# Snippet_FT232RL.net
KiCad netlist of a schematic drawn in Altium Designer
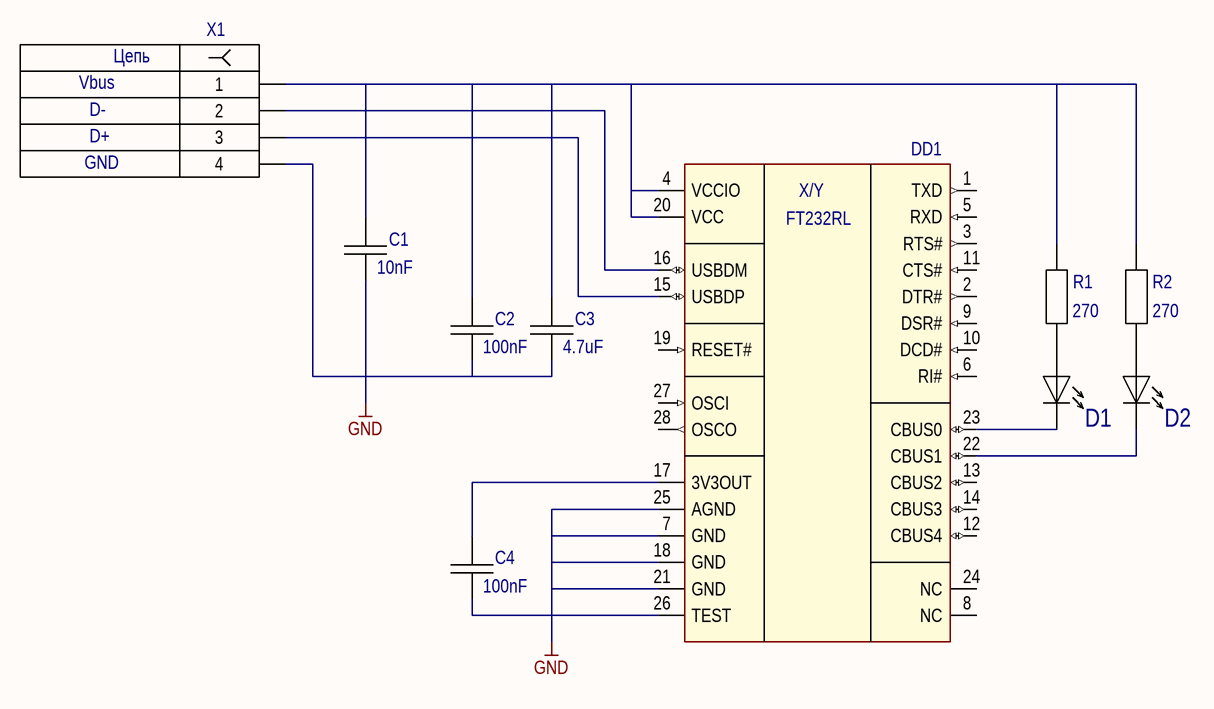
[diagram p0: Snippet_FT232RL.SchDoc]

(export (version "E")
  (design (tool "Eeschema 10.0.6"))
  (components
    (comp (ref "C1")
      (value "10nF")
      (footprint "Capacitor_0805")
      (libsource (lib "Библиотека элементов") (part "Capacitor"))
    )
    (comp (ref "C2")
      (value "100nF")
      (footprint "Capacitor_0805")
      (libsource (lib "Библиотека элементов") (part "Capacitor"))
    )
    (comp (ref "C3")
      (value "4.7uF")
      (footprint "Capacitor_0805")
      (libsource (lib "Библиотека элементов") (part "Capacitor"))
    )
    (comp (ref "C4")
      (value "100nF")
      (footprint "Capacitor_0805")
      (libsource (lib "Библиотека элементов") (part "Capacitor"))
    )
    (comp (ref "D1")
      (value "LED_2.54mm_R")
      (footprint "LED_2.54mm_R")
      (libsource (lib "Библиотека элементов") (part "LED_2.54mm_R"))
    )
    (comp (ref "D2")
      (value "LED_2.54mm_G")
      (footprint "LED_2.54mm_G")
      (libsource (lib "Библиотека элементов") (part "LED_2.54mm_G"))
    )
    (comp (ref "DD1")
      (value "FT232RL")
      (footprint "FT232RL")
      (libsource (lib "Библиотека элементов") (part "FT232RL"))
    )
    (comp (ref "R1")
      (value "270")
      (footprint "RESISTOR_SMD0805")
      (libsource (lib "Библиотека элементов") (part "Resistor_0805"))
    )
    (comp (ref "R2")
      (value "270")
      (footprint "RESISTOR_SMD0805")
      (libsource (lib "Библиотека элементов") (part "Resistor_0805"))
    )
    (comp (ref "X1")
      (value "Connector_USB_typeB")
      (footprint "Connector_USB_B")
      (libsource (lib "Библиотека элементов") (part "Connector_USB_typeB"))
    )
  )
  (nets
    (net (code "1") (name "GND") (class "Default")
      (node (ref "C1") (pin "2") (pinfunction "2_2") (pintype "passive"))
      (node (ref "C2") (pin "2") (pinfunction "2_2") (pintype "passive"))
      (node (ref "C3") (pin "2") (pinfunction "2_2") (pintype "passive"))
      (node (ref "C4") (pin "2") (pinfunction "2_2") (pintype "passive"))
      (node (ref "DD1") (pin "18") (pinfunction "GND_18") (pintype "power_in"))
      (node (ref "DD1") (pin "21") (pinfunction "GND_21") (pintype "power_in"))
      (node (ref "DD1") (pin "25") (pinfunction "AGND_25") (pintype "power_in"))
      (node (ref "DD1") (pin "26") (pinfunction "TEST_26") (pintype "power_in"))
      (node (ref "DD1") (pin "7") (pinfunction "GND_7") (pintype "power_in"))
      (node (ref "X1") (pin "4") (pinfunction "4_4") (pintype "passive"))
    )
    (net (code "2") (name "Net-(D1-Pad2)") (class "Default")
      (node (ref "D1") (pin "2") (pinfunction "2_2") (pintype "passive"))
      (node (ref "R1") (pin "1") (pinfunction "1_1") (pintype "passive"))
    )
    (net (code "3") (name "Net-(D2-Pad2)") (class "Default")
      (node (ref "D2") (pin "2") (pinfunction "2_2") (pintype "passive"))
      (node (ref "R2") (pin "1") (pinfunction "1_1") (pintype "passive"))
    )
    (net (code "4") (name "Net-(DD1-3V3OUT)") (class "Default")
      (node (ref "C4") (pin "1") (pinfunction "1_1") (pintype "passive"))
      (node (ref "DD1") (pin "17") (pinfunction "3V3OUT_17") (pintype "power_in"))
    )
    (net (code "5") (name "Net-(DD1-CBUS0)") (class "Default")
      (node (ref "D1") (pin "1") (pinfunction "1_1") (pintype "passive"))
      (node (ref "DD1") (pin "23") (pinfunction "CBUS0_23") (pintype "bidirectional"))
    )
    (net (code "6") (name "Net-(DD1-CBUS1)") (class "Default")
      (node (ref "D2") (pin "1") (pinfunction "1_1") (pintype "passive"))
      (node (ref "DD1") (pin "22") (pinfunction "CBUS1_22") (pintype "bidirectional"))
    )
    (net (code "7") (name "Net-(DD1-USBDM)") (class "Default")
      (node (ref "DD1") (pin "16") (pinfunction "USBDM_16") (pintype "bidirectional"))
      (node (ref "X1") (pin "2") (pinfunction "2_2") (pintype "passive"))
    )
    (net (code "8") (name "Net-(DD1-USBDP)") (class "Default")
      (node (ref "DD1") (pin "15") (pinfunction "USBDP_15") (pintype "bidirectional"))
      (node (ref "X1") (pin "3") (pinfunction "3_3") (pintype "passive"))
    )
    (net (code "9") (name "Net-(DD1-VCC)") (class "Default")
      (node (ref "C1") (pin "1") (pinfunction "1_1") (pintype "passive"))
      (node (ref "C2") (pin "1") (pinfunction "1_1") (pintype "passive"))
      (node (ref "C3") (pin "1") (pinfunction "1_1") (pintype "passive"))
      (node (ref "DD1") (pin "20") (pinfunction "VCC_20") (pintype "power_in"))
      (node (ref "DD1") (pin "4") (pinfunction "VCCIO_4") (pintype "power_in"))
      (node (ref "R1") (pin "2") (pinfunction "2_2") (pintype "passive"))
      (node (ref "R2") (pin "2") (pinfunction "2_2") (pintype "passive"))
      (node (ref "X1") (pin "1") (pinfunction "1_1") (pintype "passive"))
    )
    (net (code "10") (name "unconnected-(DD1-CBUS2-Pad13)") (class "Default")
      (node (ref "DD1") (pin "13") (pinfunction "CBUS2_13") (pintype "bidirectional"))
    )
    (net (code "11") (name "unconnected-(DD1-CBUS3-Pad14)") (class "Default")
      (node (ref "DD1") (pin "14") (pinfunction "CBUS3_14") (pintype "bidirectional"))
    )
    (net (code "12") (name "unconnected-(DD1-CBUS4-Pad12)") (class "Default")
      (node (ref "DD1") (pin "12") (pinfunction "CBUS4_12") (pintype "bidirectional"))
    )
    (net (code "13") (name "unconnected-(DD1-CTS#-Pad11)") (class "Default")
      (node (ref "DD1") (pin "11") (pinfunction "CTS#_11") (pintype "input"))
    )
    (net (code "14") (name "unconnected-(DD1-DCD#-Pad10)") (class "Default")
      (node (ref "DD1") (pin "10") (pinfunction "DCD#_10") (pintype "input"))
    )
    (net (code "15") (name "unconnected-(DD1-DSR#-Pad9)") (class "Default")
      (node (ref "DD1") (pin "9") (pinfunction "DSR#_9") (pintype "input"))
    )
    (net (code "16") (name "unconnected-(DD1-DTR#-Pad2)") (class "Default")
      (node (ref "DD1") (pin "2") (pinfunction "DTR#_2") (pintype "output"))
    )
    (net (code "17") (name "unconnected-(DD1-NC-Pad8)") (class "Default")
      (node (ref "DD1") (pin "8") (pinfunction "NC_8") (pintype "passive"))
    )
    (net (code "18") (name "unconnected-(DD1-NC-Pad24)") (class "Default")
      (node (ref "DD1") (pin "24") (pinfunction "NC_24") (pintype "passive"))
    )
    (net (code "19") (name "unconnected-(DD1-OSCI-Pad27)") (class "Default")
      (node (ref "DD1") (pin "27") (pinfunction "OSCI_27") (pintype "input"))
    )
    (net (code "20") (name "unconnected-(DD1-OSCO-Pad28)") (class "Default")
      (node (ref "DD1") (pin "28") (pinfunction "OSCO_28") (pintype "output"))
    )
    (net (code "21") (name "unconnected-(DD1-RESET#-Pad19)") (class "Default")
      (node (ref "DD1") (pin "19") (pinfunction "RESET#_19") (pintype "input"))
    )
    (net (code "22") (name "unconnected-(DD1-RI#-Pad6)") (class "Default")
      (node (ref "DD1") (pin "6") (pinfunction "RI#_6") (pintype "input"))
    )
    (net (code "23") (name "unconnected-(DD1-RTS#-Pad3)") (class "Default")
      (node (ref "DD1") (pin "3") (pinfunction "RTS#_3") (pintype "output"))
    )
    (net (code "24") (name "unconnected-(DD1-RXD-Pad5)") (class "Default")
      (node (ref "DD1") (pin "5") (pinfunction "RXD_5") (pintype "input"))
    )
    (net (code "25") (name "unconnected-(DD1-TXD-Pad1)") (class "Default")
      (node (ref "DD1") (pin "1") (pinfunction "TXD_1") (pintype "output"))
    )
  )
)
